# Light_Tester.net
KiCad netlist of a schematic drawn in EAGLE
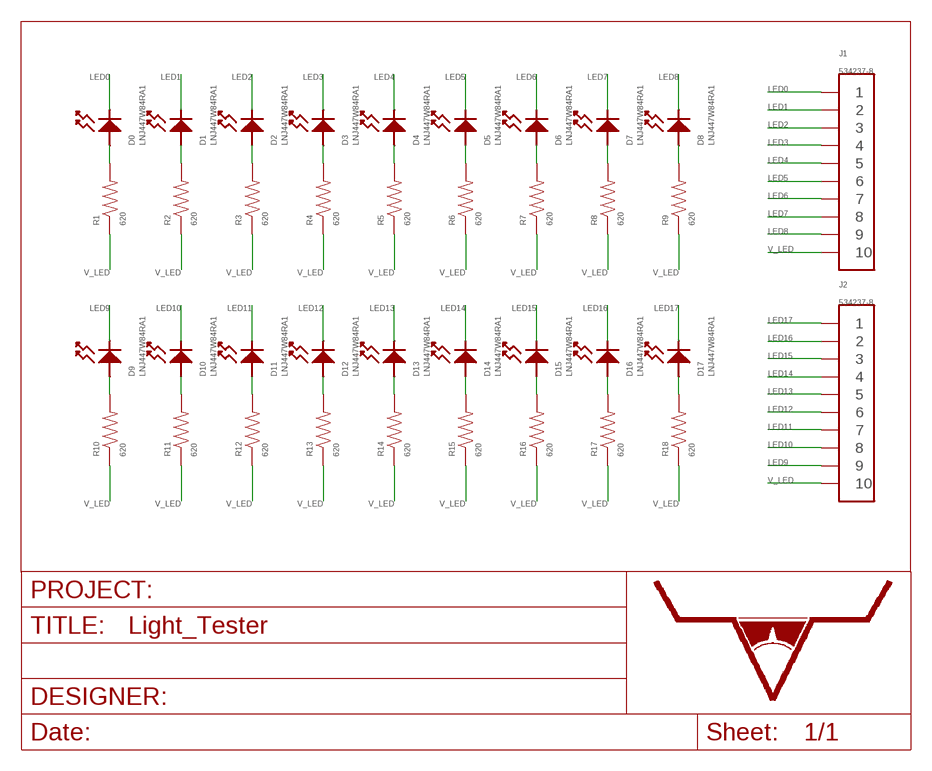
[diagram p0: schematic, sheet 1]

(export (version "E")
  (design (tool "Eeschema 10.0.6"))
  (components
    (comp (ref "D0")
      (value "LNJ447W84RA1")
      (footprint "eagle-import:LED_0402")
      (libsource (lib "eagle-import") (part "LED_SINGLE0402"))
    )
    (comp (ref "D1")
      (value "LNJ447W84RA1")
      (footprint "eagle-import:LED_0402")
      (libsource (lib "eagle-import") (part "LED_SINGLE0402"))
    )
    (comp (ref "D2")
      (value "LNJ447W84RA1")
      (footprint "eagle-import:LED_0402")
      (libsource (lib "eagle-import") (part "LED_SINGLE0402"))
    )
    (comp (ref "D3")
      (value "LNJ447W84RA1")
      (footprint "eagle-import:LED_0402")
      (libsource (lib "eagle-import") (part "LED_SINGLE0402"))
    )
    (comp (ref "D4")
      (value "LNJ447W84RA1")
      (footprint "eagle-import:LED_0402")
      (libsource (lib "eagle-import") (part "LED_SINGLE0402"))
    )
    (comp (ref "D5")
      (value "LNJ447W84RA1")
      (footprint "eagle-import:LED_0402")
      (libsource (lib "eagle-import") (part "LED_SINGLE0402"))
    )
    (comp (ref "D6")
      (value "LNJ447W84RA1")
      (footprint "eagle-import:LED_0402")
      (libsource (lib "eagle-import") (part "LED_SINGLE0402"))
    )
    (comp (ref "D7")
      (value "LNJ447W84RA1")
      (footprint "eagle-import:LED_0402")
      (libsource (lib "eagle-import") (part "LED_SINGLE0402"))
    )
    (comp (ref "D8")
      (value "LNJ447W84RA1")
      (footprint "eagle-import:LED_0402")
      (libsource (lib "eagle-import") (part "LED_SINGLE0402"))
    )
    (comp (ref "D9")
      (value "LNJ447W84RA1")
      (footprint "eagle-import:LED_0402")
      (libsource (lib "eagle-import") (part "LED_SINGLE0402"))
    )
    (comp (ref "D10")
      (value "LNJ447W84RA1")
      (footprint "eagle-import:LED_0402")
      (libsource (lib "eagle-import") (part "LED_SINGLE0402"))
    )
    (comp (ref "D11")
      (value "LNJ447W84RA1")
      (footprint "eagle-import:LED_0402")
      (libsource (lib "eagle-import") (part "LED_SINGLE0402"))
    )
    (comp (ref "D12")
      (value "LNJ447W84RA1")
      (footprint "eagle-import:LED_0402")
      (libsource (lib "eagle-import") (part "LED_SINGLE0402"))
    )
    (comp (ref "D13")
      (value "LNJ447W84RA1")
      (footprint "eagle-import:LED_0402")
      (libsource (lib "eagle-import") (part "LED_SINGLE0402"))
    )
    (comp (ref "D14")
      (value "LNJ447W84RA1")
      (footprint "eagle-import:LED_0402")
      (libsource (lib "eagle-import") (part "LED_SINGLE0402"))
    )
    (comp (ref "D15")
      (value "LNJ447W84RA1")
      (footprint "eagle-import:LED_0402")
      (libsource (lib "eagle-import") (part "LED_SINGLE0402"))
    )
    (comp (ref "D16")
      (value "LNJ447W84RA1")
      (footprint "eagle-import:LED_0402")
      (libsource (lib "eagle-import") (part "LED_SINGLE0402"))
    )
    (comp (ref "D17")
      (value "LNJ447W84RA1")
      (footprint "eagle-import:LED_0402")
      (libsource (lib "eagle-import") (part "LED_SINGLE0402"))
    )
    (comp (ref "J1")
      (value "534237-8")
      (footprint "eagle-import:HEADER_01X10_PTH")
      (libsource (lib "eagle-import") (part "PH_1X10PTH"))
    )
    (comp (ref "J2")
      (value "534237-8")
      (footprint "eagle-import:HEADER_01X10_PTH")
      (libsource (lib "eagle-import") (part "PH_1X10PTH"))
    )
    (comp (ref "R1")
      (value "620")
      (footprint "eagle-import:0402")
      (libsource (lib "eagle-import") (part "RESISTOR0402"))
    )
    (comp (ref "R2")
      (value "620")
      (footprint "eagle-import:0402")
      (libsource (lib "eagle-import") (part "RESISTOR0402"))
    )
    (comp (ref "R3")
      (value "620")
      (footprint "eagle-import:0402")
      (libsource (lib "eagle-import") (part "RESISTOR0402"))
    )
    (comp (ref "R4")
      (value "620")
      (footprint "eagle-import:0402")
      (libsource (lib "eagle-import") (part "RESISTOR0402"))
    )
    (comp (ref "R5")
      (value "620")
      (footprint "eagle-import:0402")
      (libsource (lib "eagle-import") (part "RESISTOR0402"))
    )
    (comp (ref "R6")
      (value "620")
      (footprint "eagle-import:0402")
      (libsource (lib "eagle-import") (part "RESISTOR0402"))
    )
    (comp (ref "R7")
      (value "620")
      (footprint "eagle-import:0402")
      (libsource (lib "eagle-import") (part "RESISTOR0402"))
    )
    (comp (ref "R8")
      (value "620")
      (footprint "eagle-import:0402")
      (libsource (lib "eagle-import") (part "RESISTOR0402"))
    )
    (comp (ref "R9")
      (value "620")
      (footprint "eagle-import:0402")
      (libsource (lib "eagle-import") (part "RESISTOR0402"))
    )
    (comp (ref "R10")
      (value "620")
      (footprint "eagle-import:0402")
      (libsource (lib "eagle-import") (part "RESISTOR0402"))
    )
    (comp (ref "R11")
      (value "620")
      (footprint "eagle-import:0402")
      (libsource (lib "eagle-import") (part "RESISTOR0402"))
    )
    (comp (ref "R12")
      (value "620")
      (footprint "eagle-import:0402")
      (libsource (lib "eagle-import") (part "RESISTOR0402"))
    )
    (comp (ref "R13")
      (value "620")
      (footprint "eagle-import:0402")
      (libsource (lib "eagle-import") (part "RESISTOR0402"))
    )
    (comp (ref "R14")
      (value "620")
      (footprint "eagle-import:0402")
      (libsource (lib "eagle-import") (part "RESISTOR0402"))
    )
    (comp (ref "R15")
      (value "620")
      (footprint "eagle-import:0402")
      (libsource (lib "eagle-import") (part "RESISTOR0402"))
    )
    (comp (ref "R16")
      (value "620")
      (footprint "eagle-import:0402")
      (libsource (lib "eagle-import") (part "RESISTOR0402"))
    )
    (comp (ref "R17")
      (value "620")
      (footprint "eagle-import:0402")
      (libsource (lib "eagle-import") (part "RESISTOR0402"))
    )
    (comp (ref "R18")
      (value "620")
      (footprint "eagle-import:0402")
      (libsource (lib "eagle-import") (part "RESISTOR0402"))
    )
    (comp (ref "U$1")
      (value "LHE_FRAME")
      (footprint "eagle-import:LHE_FRAME")
      (fields
        (field (name "DNAME") "Parker Dillmann")
        (field (name "PNAME") "Light Tester For Tommy System")
        (field (name "REVNUM") "REV 0")
      )
      (libsource (lib "eagle-import") (part "LHE_FRAME"))
    )
  )
  (nets
    (net (code "1") (name "/LED0") (class "Default")
      (node (ref "D0") (pin "CATHODE") (pinfunction "CATHODE_CATHODE") (pintype "bidirectional"))
      (node (ref "J1") (pin "1") (pinfunction "1_1") (pintype "bidirectional"))
    )
    (net (code "2") (name "/LED1") (class "Default")
      (node (ref "D1") (pin "CATHODE") (pinfunction "CATHODE_CATHODE") (pintype "bidirectional"))
      (node (ref "J1") (pin "2") (pinfunction "2_2") (pintype "bidirectional"))
    )
    (net (code "3") (name "/LED2") (class "Default")
      (node (ref "D2") (pin "CATHODE") (pinfunction "CATHODE_CATHODE") (pintype "bidirectional"))
      (node (ref "J1") (pin "3") (pinfunction "3_3") (pintype "bidirectional"))
    )
    (net (code "4") (name "/LED3") (class "Default")
      (node (ref "D3") (pin "CATHODE") (pinfunction "CATHODE_CATHODE") (pintype "bidirectional"))
      (node (ref "J1") (pin "4") (pinfunction "4_4") (pintype "bidirectional"))
    )
    (net (code "5") (name "/LED4") (class "Default")
      (node (ref "D4") (pin "CATHODE") (pinfunction "CATHODE_CATHODE") (pintype "bidirectional"))
      (node (ref "J1") (pin "5") (pinfunction "5_5") (pintype "bidirectional"))
    )
    (net (code "6") (name "/LED5") (class "Default")
      (node (ref "D5") (pin "CATHODE") (pinfunction "CATHODE_CATHODE") (pintype "bidirectional"))
      (node (ref "J1") (pin "6") (pinfunction "6_6") (pintype "bidirectional"))
    )
    (net (code "7") (name "/LED6") (class "Default")
      (node (ref "D6") (pin "CATHODE") (pinfunction "CATHODE_CATHODE") (pintype "bidirectional"))
      (node (ref "J1") (pin "7") (pinfunction "7_7") (pintype "bidirectional"))
    )
    (net (code "8") (name "/LED7") (class "Default")
      (node (ref "D7") (pin "CATHODE") (pinfunction "CATHODE_CATHODE") (pintype "bidirectional"))
      (node (ref "J1") (pin "8") (pinfunction "8_8") (pintype "bidirectional"))
    )
    (net (code "9") (name "/LED8") (class "Default")
      (node (ref "D8") (pin "CATHODE") (pinfunction "CATHODE_CATHODE") (pintype "bidirectional"))
      (node (ref "J1") (pin "9") (pinfunction "9_9") (pintype "bidirectional"))
    )
    (net (code "10") (name "/LED9") (class "Default")
      (node (ref "D9") (pin "CATHODE") (pinfunction "CATHODE_CATHODE") (pintype "bidirectional"))
      (node (ref "J2") (pin "9") (pinfunction "9_9") (pintype "bidirectional"))
    )
    (net (code "11") (name "/LED10") (class "Default")
      (node (ref "D10") (pin "CATHODE") (pinfunction "CATHODE_CATHODE") (pintype "bidirectional"))
      (node (ref "J2") (pin "8") (pinfunction "8_8") (pintype "bidirectional"))
    )
    (net (code "12") (name "/LED11") (class "Default")
      (node (ref "D11") (pin "CATHODE") (pinfunction "CATHODE_CATHODE") (pintype "bidirectional"))
      (node (ref "J2") (pin "7") (pinfunction "7_7") (pintype "bidirectional"))
    )
    (net (code "13") (name "/LED12") (class "Default")
      (node (ref "D12") (pin "CATHODE") (pinfunction "CATHODE_CATHODE") (pintype "bidirectional"))
      (node (ref "J2") (pin "6") (pinfunction "6_6") (pintype "bidirectional"))
    )
    (net (code "14") (name "/LED13") (class "Default")
      (node (ref "D13") (pin "CATHODE") (pinfunction "CATHODE_CATHODE") (pintype "bidirectional"))
      (node (ref "J2") (pin "5") (pinfunction "5_5") (pintype "bidirectional"))
    )
    (net (code "15") (name "/LED14") (class "Default")
      (node (ref "D14") (pin "CATHODE") (pinfunction "CATHODE_CATHODE") (pintype "bidirectional"))
      (node (ref "J2") (pin "4") (pinfunction "4_4") (pintype "bidirectional"))
    )
    (net (code "16") (name "/LED15") (class "Default")
      (node (ref "D15") (pin "CATHODE") (pinfunction "CATHODE_CATHODE") (pintype "bidirectional"))
      (node (ref "J2") (pin "3") (pinfunction "3_3") (pintype "bidirectional"))
    )
    (net (code "17") (name "/LED16") (class "Default")
      (node (ref "D16") (pin "CATHODE") (pinfunction "CATHODE_CATHODE") (pintype "bidirectional"))
      (node (ref "J2") (pin "2") (pinfunction "2_2") (pintype "bidirectional"))
    )
    (net (code "18") (name "/LED17") (class "Default")
      (node (ref "D17") (pin "CATHODE") (pinfunction "CATHODE_CATHODE") (pintype "bidirectional"))
      (node (ref "J2") (pin "1") (pinfunction "1_1") (pintype "bidirectional"))
    )
    (net (code "19") (name "/V_LED") (class "Default")
      (node (ref "J1") (pin "10") (pinfunction "10_10") (pintype "bidirectional"))
      (node (ref "J2") (pin "10") (pinfunction "10_10") (pintype "bidirectional"))
      (node (ref "R1") (pin "1") (pinfunction "1_1") (pintype "passive"))
      (node (ref "R10") (pin "1") (pinfunction "1_1") (pintype "passive"))
      (node (ref "R11") (pin "1") (pinfunction "1_1") (pintype "passive"))
      (node (ref "R12") (pin "1") (pinfunction "1_1") (pintype "passive"))
      (node (ref "R13") (pin "1") (pinfunction "1_1") (pintype "passive"))
      (node (ref "R14") (pin "1") (pinfunction "1_1") (pintype "passive"))
      (node (ref "R15") (pin "1") (pinfunction "1_1") (pintype "passive"))
      (node (ref "R16") (pin "1") (pinfunction "1_1") (pintype "passive"))
      (node (ref "R17") (pin "1") (pinfunction "1_1") (pintype "passive"))
      (node (ref "R18") (pin "1") (pinfunction "1_1") (pintype "passive"))
      (node (ref "R2") (pin "1") (pinfunction "1_1") (pintype "passive"))
      (node (ref "R3") (pin "1") (pinfunction "1_1") (pintype "passive"))
      (node (ref "R4") (pin "1") (pinfunction "1_1") (pintype "passive"))
      (node (ref "R5") (pin "1") (pinfunction "1_1") (pintype "passive"))
      (node (ref "R6") (pin "1") (pinfunction "1_1") (pintype "passive"))
      (node (ref "R7") (pin "1") (pinfunction "1_1") (pintype "passive"))
      (node (ref "R8") (pin "1") (pinfunction "1_1") (pintype "passive"))
      (node (ref "R9") (pin "1") (pinfunction "1_1") (pintype "passive"))
    )
    (net (code "20") (name "Net-(D0-PadANODE)") (class "Default")
      (node (ref "D0") (pin "ANODE") (pinfunction "ANODE_ANODE") (pintype "bidirectional"))
      (node (ref "R1") (pin "2") (pinfunction "2_2") (pintype "passive"))
    )
    (net (code "21") (name "Net-(D1-PadANODE)") (class "Default")
      (node (ref "D1") (pin "ANODE") (pinfunction "ANODE_ANODE") (pintype "bidirectional"))
      (node (ref "R2") (pin "2") (pinfunction "2_2") (pintype "passive"))
    )
    (net (code "22") (name "Net-(D2-PadANODE)") (class "Default")
      (node (ref "D2") (pin "ANODE") (pinfunction "ANODE_ANODE") (pintype "bidirectional"))
      (node (ref "R3") (pin "2") (pinfunction "2_2") (pintype "passive"))
    )
    (net (code "23") (name "Net-(D3-PadANODE)") (class "Default")
      (node (ref "D3") (pin "ANODE") (pinfunction "ANODE_ANODE") (pintype "bidirectional"))
      (node (ref "R4") (pin "2") (pinfunction "2_2") (pintype "passive"))
    )
    (net (code "24") (name "Net-(D4-PadANODE)") (class "Default")
      (node (ref "D4") (pin "ANODE") (pinfunction "ANODE_ANODE") (pintype "bidirectional"))
      (node (ref "R5") (pin "2") (pinfunction "2_2") (pintype "passive"))
    )
    (net (code "25") (name "Net-(D5-PadANODE)") (class "Default")
      (node (ref "D5") (pin "ANODE") (pinfunction "ANODE_ANODE") (pintype "bidirectional"))
      (node (ref "R6") (pin "2") (pinfunction "2_2") (pintype "passive"))
    )
    (net (code "26") (name "Net-(D6-PadANODE)") (class "Default")
      (node (ref "D6") (pin "ANODE") (pinfunction "ANODE_ANODE") (pintype "bidirectional"))
      (node (ref "R7") (pin "2") (pinfunction "2_2") (pintype "passive"))
    )
    (net (code "27") (name "Net-(D7-PadANODE)") (class "Default")
      (node (ref "D7") (pin "ANODE") (pinfunction "ANODE_ANODE") (pintype "bidirectional"))
      (node (ref "R8") (pin "2") (pinfunction "2_2") (pintype "passive"))
    )
    (net (code "28") (name "Net-(D8-PadANODE)") (class "Default")
      (node (ref "D8") (pin "ANODE") (pinfunction "ANODE_ANODE") (pintype "bidirectional"))
      (node (ref "R9") (pin "2") (pinfunction "2_2") (pintype "passive"))
    )
    (net (code "29") (name "Net-(D9-PadANODE)") (class "Default")
      (node (ref "D9") (pin "ANODE") (pinfunction "ANODE_ANODE") (pintype "bidirectional"))
      (node (ref "R10") (pin "2") (pinfunction "2_2") (pintype "passive"))
    )
    (net (code "30") (name "Net-(D10-PadANODE)") (class "Default")
      (node (ref "D10") (pin "ANODE") (pinfunction "ANODE_ANODE") (pintype "bidirectional"))
      (node (ref "R11") (pin "2") (pinfunction "2_2") (pintype "passive"))
    )
    (net (code "31") (name "Net-(D11-PadANODE)") (class "Default")
      (node (ref "D11") (pin "ANODE") (pinfunction "ANODE_ANODE") (pintype "bidirectional"))
      (node (ref "R12") (pin "2") (pinfunction "2_2") (pintype "passive"))
    )
    (net (code "32") (name "Net-(D12-PadANODE)") (class "Default")
      (node (ref "D12") (pin "ANODE") (pinfunction "ANODE_ANODE") (pintype "bidirectional"))
      (node (ref "R13") (pin "2") (pinfunction "2_2") (pintype "passive"))
    )
    (net (code "33") (name "Net-(D13-PadANODE)") (class "Default")
      (node (ref "D13") (pin "ANODE") (pinfunction "ANODE_ANODE") (pintype "bidirectional"))
      (node (ref "R14") (pin "2") (pinfunction "2_2") (pintype "passive"))
    )
    (net (code "34") (name "Net-(D14-PadANODE)") (class "Default")
      (node (ref "D14") (pin "ANODE") (pinfunction "ANODE_ANODE") (pintype "bidirectional"))
      (node (ref "R15") (pin "2") (pinfunction "2_2") (pintype "passive"))
    )
    (net (code "35") (name "Net-(D15-PadANODE)") (class "Default")
      (node (ref "D15") (pin "ANODE") (pinfunction "ANODE_ANODE") (pintype "bidirectional"))
      (node (ref "R16") (pin "2") (pinfunction "2_2") (pintype "passive"))
    )
    (net (code "36") (name "Net-(D16-PadANODE)") (class "Default")
      (node (ref "D16") (pin "ANODE") (pinfunction "ANODE_ANODE") (pintype "bidirectional"))
      (node (ref "R17") (pin "2") (pinfunction "2_2") (pintype "passive"))
    )
    (net (code "37") (name "Net-(D17-PadANODE)") (class "Default")
      (node (ref "D17") (pin "ANODE") (pinfunction "ANODE_ANODE") (pintype "bidirectional"))
      (node (ref "R18") (pin "2") (pinfunction "2_2") (pintype "passive"))
    )
  )
)
